# SMOOTHIELASER_BREAKOUT.net
KiCad netlist of a schematic drawn in EAGLE
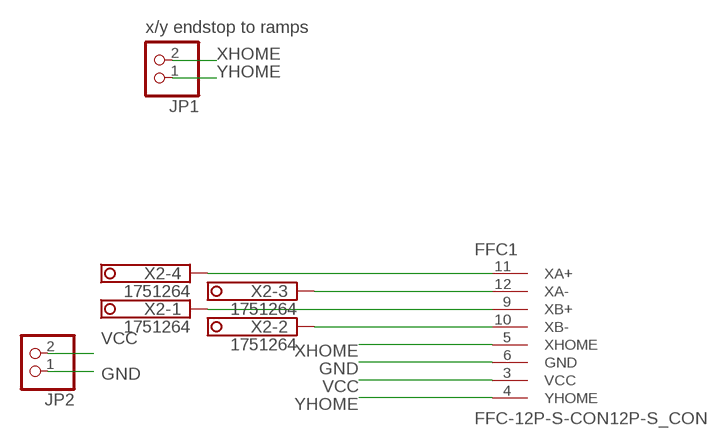
[diagram p0: schematic, sheet 1]

(export (version "E")
  (design (tool "Eeschema 10.0.6"))
  (components
    (comp (ref "FFC1")
      (value "FFC-12P-S-CON12P-S_CON")
      (footprint "eagle-import:FFC")
      (libsource (lib "eagle-import") (part "FFC-12P-S-CON12P-S_CON"))
    )
    (comp (ref "JP1")
      (value "PINHD-1X2")
      (footprint "eagle-import:1X02")
      (libsource (lib "eagle-import") (part "PINHD-1X2"))
    )
    (comp (ref "JP2")
      (value "PINHD-1X2")
      (footprint "eagle-import:1X02")
      (libsource (lib "eagle-import") (part "PINHD-1X2"))
    )
    (comp (ref "X2")
      (value "1751264")
      (footprint "eagle-import:1751264")
      (libsource (lib "eagle-import") (part "1751264"))
    )
  )
  (nets
    (net (code "1") (name "/GND") (class "Default")
      (node (ref "FFC1") (pin "6") (pinfunction "GND_6") (pintype "power_in"))
      (node (ref "JP2") (pin "1") (pinfunction "1_1") (pintype "passive"))
    )
    (net (code "2") (name "/VCC") (class "Default")
      (node (ref "FFC1") (pin "3") (pinfunction "VCC_3") (pintype "power_in"))
      (node (ref "JP2") (pin "2") (pinfunction "2_2") (pintype "passive"))
    )
    (net (code "3") (name "/XHOME") (class "Default")
      (node (ref "FFC1") (pin "5") (pinfunction "XHOME_5") (pintype "bidirectional"))
      (node (ref "JP1") (pin "2") (pinfunction "2_2") (pintype "passive"))
    )
    (net (code "4") (name "/YHOME") (class "Default")
      (node (ref "FFC1") (pin "4") (pinfunction "YHOME_4") (pintype "bidirectional"))
      (node (ref "JP1") (pin "1") (pinfunction "1_1") (pintype "passive"))
    )
    (net (code "5") (name "Net-(FFC1-XA+)") (class "Default")
      (node (ref "FFC1") (pin "11") (pinfunction "XA+_11") (pintype "bidirectional"))
      (node (ref "X2") (pin "4") (pinfunction "K_4") (pintype "passive"))
    )
    (net (code "6") (name "Net-(FFC1-XA-)") (class "Default")
      (node (ref "FFC1") (pin "12") (pinfunction "XA-_12") (pintype "bidirectional"))
      (node (ref "X2") (pin "3") (pinfunction "K_3") (pintype "passive"))
    )
    (net (code "7") (name "Net-(FFC1-XB+)") (class "Default")
      (node (ref "FFC1") (pin "9") (pinfunction "XB+_9") (pintype "bidirectional"))
      (node (ref "X2") (pin "1") (pinfunction "K_1") (pintype "passive"))
    )
    (net (code "8") (name "Net-(FFC1-XB-)") (class "Default")
      (node (ref "FFC1") (pin "10") (pinfunction "XB-_10") (pintype "bidirectional"))
      (node (ref "X2") (pin "2") (pinfunction "K_2") (pintype "passive"))
    )
  )
)
